# SingleSystem1.net
KiCad netlist of a schematic drawn in EAGLE
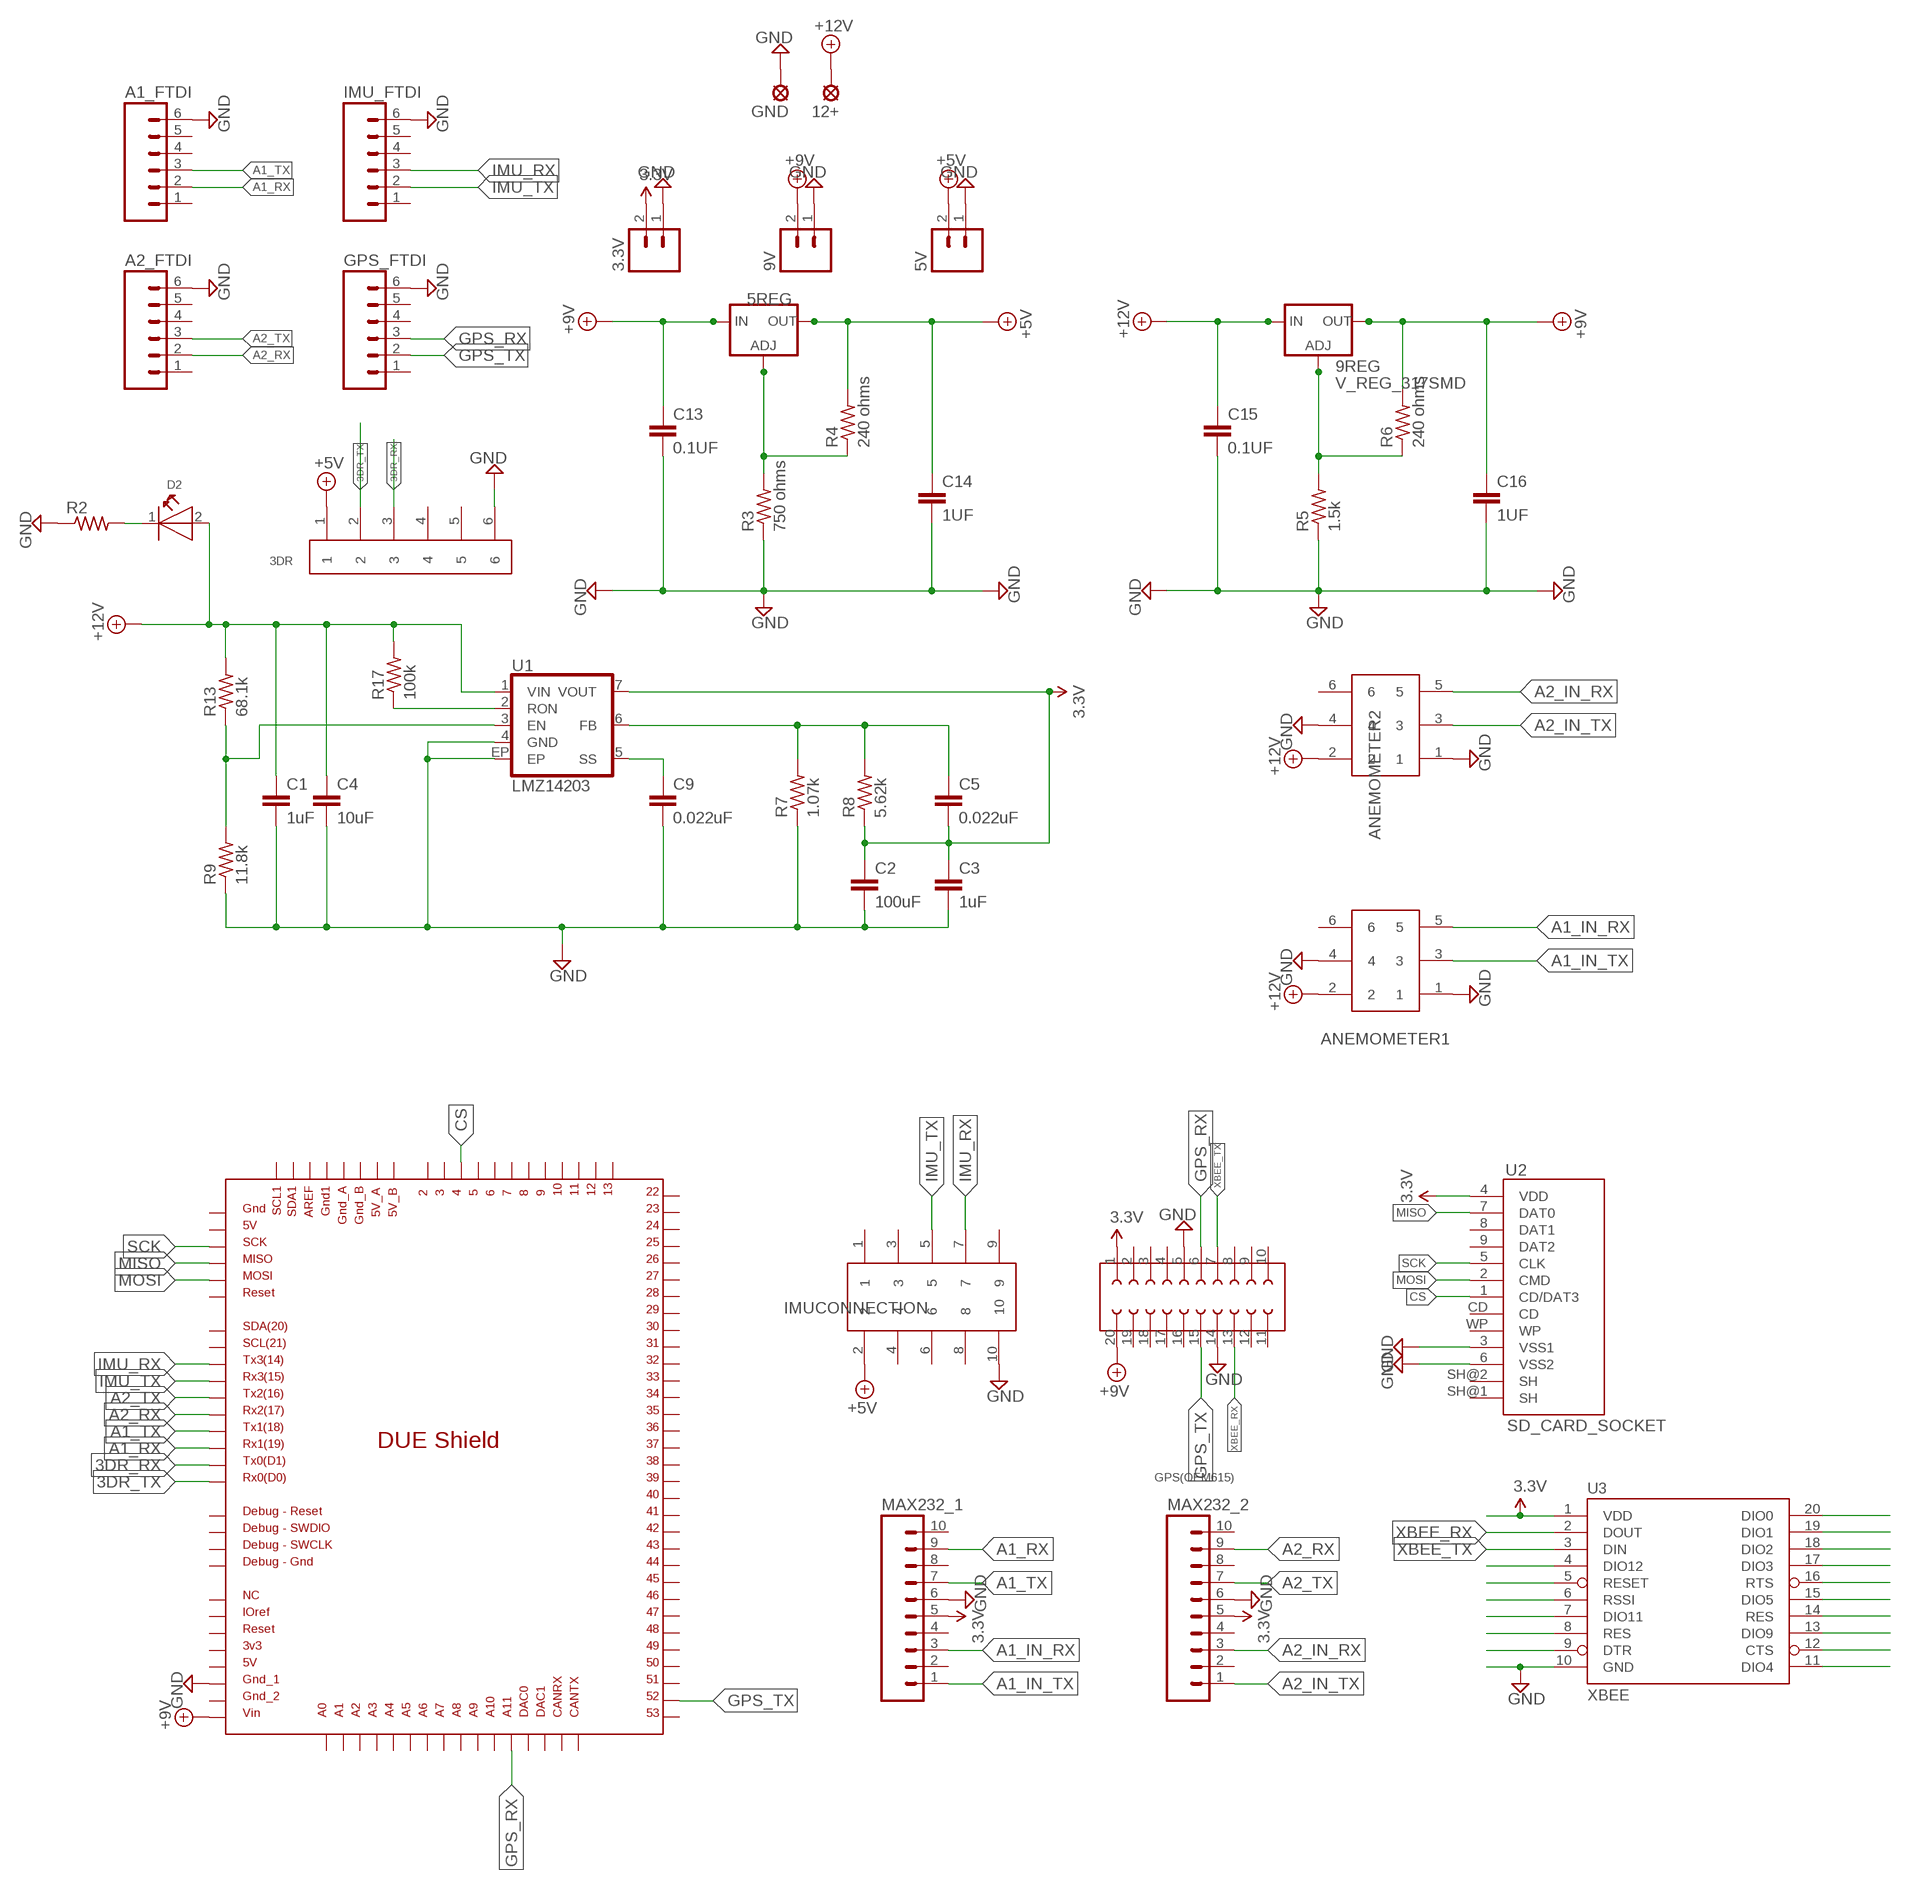
[diagram p0: schematic, sheet 1]

(export (version "E")
  (design (tool "Eeschema 10.0.6"))
  (components
    (comp (ref "3.3V")
      (value "M02")
      (footprint "eagle-import:02P")
      (libsource (lib "eagle-import") (part "M02"))
    )
    (comp (ref "3DR")
      (value "653006114822")
      (footprint "eagle-import:653006114822")
      (libsource (lib "eagle-import") (part "653006114822"))
    )
    (comp (ref "5REG")
      (value "V_REG_317SMD")
      (footprint "eagle-import:SOT223")
      (libsource (lib "eagle-import") (part "V_REG_317SMD"))
    )
    (comp (ref "5V")
      (value "M02")
      (footprint "eagle-import:02P")
      (libsource (lib "eagle-import") (part "M02"))
    )
    (comp (ref "9REG")
      (value "V_REG_317SMD")
      (footprint "eagle-import:SOT223")
      (libsource (lib "eagle-import") (part "V_REG_317SMD"))
    )
    (comp (ref "9V")
      (value "M02")
      (footprint "eagle-import:02P")
      (libsource (lib "eagle-import") (part "M02"))
    )
    (comp (ref "12+")
      (value "SE14")
      (footprint "eagle-import:SE14")
      (libsource (lib "eagle-import") (part "SE14"))
    )
    (comp (ref "A1_FTDI")
      (value "M06")
      (footprint "eagle-import:06P")
      (libsource (lib "eagle-import") (part "M06"))
    )
    (comp (ref "A2_FTDI")
      (value "M06")
      (footprint "eagle-import:06P")
      (libsource (lib "eagle-import") (part "M06"))
    )
    (comp (ref "ANEMOMETER1")
      (value "61200622323")
      (footprint "eagle-import:61200622323")
      (libsource (lib "eagle-import") (part "61200622323"))
    )
    (comp (ref "ANEMOMETER2")
      (value "61200622323")
      (footprint "eagle-import:61200622323")
      (libsource (lib "eagle-import") (part "61200622323"))
    )
    (comp (ref "C1")
      (value "1uF")
      (footprint "eagle-import:0805")
      (fields (field (name "MF") "VISHAY/SPRAGUE") (field (name "MPN") "1C10Z5U104M050R"))
      (libsource (lib "eagle-import") (part "1UF-25V-10%(0805)"))
    )
    (comp (ref "C2")
      (value "100uF")
      (footprint "eagle-import:1206")
      (libsource (lib "eagle-import") (part "CAP1206"))
    )
    (comp (ref "C3")
      (value "1uF")
      (footprint "eagle-import:0805")
      (fields (field (name "MF") "VISHAY/SPRAGUE") (field (name "MPN") "1C10Z5U104M050R"))
      (libsource (lib "eagle-import") (part "1UF-25V-10%(0805)"))
    )
    (comp (ref "C4")
      (value "10uF")
      (footprint "eagle-import:0805")
      (libsource (lib "eagle-import") (part "CAP0805"))
    )
    (comp (ref "C5")
      (value "0.022uF")
      (footprint "eagle-import:0603-CAP")
      (libsource (lib "eagle-import") (part "CAP0603-CAP"))
    )
    (comp (ref "C9")
      (value "0.022uF")
      (footprint "eagle-import:0603-CAP")
      (libsource (lib "eagle-import") (part "CAP0603-CAP"))
    )
    (comp (ref "C13")
      (value "0.1UF")
      (footprint "eagle-import:0805")
      (libsource (lib "eagle-import") (part "1UF-25V-10%(0805)"))
    )
    (comp (ref "C14")
      (value "1UF")
      (footprint "eagle-import:0805")
      (libsource (lib "eagle-import") (part "1UF-25V-10%(0805)"))
    )
    (comp (ref "C15")
      (value "0.1UF")
      (footprint "eagle-import:0805")
      (libsource (lib "eagle-import") (part "1UF-25V-10%(0805)"))
    )
    (comp (ref "C16")
      (value "1UF")
      (footprint "eagle-import:0805")
      (libsource (lib "eagle-import") (part "1UF-25V-10%(0805)"))
    )
    (comp (ref "D2")
      (value "WL-SMCW-150120BS75000-B")
      (footprint "eagle-import:1206")
      (fields
        (field (name "MANUFACTURER") "Würth Elektronik eiSos GmbH")
        (field (name "CREATED-BY") "Christin Otto")
      )
      (libsource (lib "eagle-import") (part "WL-SMCW-150120BS75000-B"))
    )
    (comp (ref "GND")
      (value "SE14")
      (footprint "eagle-import:SE14")
      (libsource (lib "eagle-import") (part "SE14"))
    )
    (comp (ref "GPS(OEM615)")
      (value "62002021821")
      (footprint "eagle-import:62002021821")
      (libsource (lib "eagle-import") (part "62002021821"))
    )
    (comp (ref "GPS_FTDI")
      (value "M06")
      (footprint "eagle-import:06P")
      (libsource (lib "eagle-import") (part "M06"))
    )
    (comp (ref "IMUCONNECTION")
      (value "62501021621")
      (footprint "eagle-import:62501021621")
      (libsource (lib "eagle-import") (part "62501021621"))
    )
    (comp (ref "IMU_FTDI")
      (value "M06")
      (footprint "eagle-import:06P")
      (libsource (lib "eagle-import") (part "M06"))
    )
    (comp (ref "MAX232_1")
      (value "M10")
      (footprint "eagle-import:10P")
      (libsource (lib "eagle-import") (part "M10"))
    )
    (comp (ref "MAX232_2")
      (value "M10")
      (footprint "eagle-import:10P")
      (libsource (lib "eagle-import") (part "M10"))
    )
    (comp (ref "R2")
      (value "R-US_M2012")
      (footprint "eagle-import:M2012")
      (libsource (lib "eagle-import") (part "resistor_R-US_M2012"))
    )
    (comp (ref "R3")
      (value "750 ohms")
      (footprint "eagle-import:M2012")
      (libsource (lib "eagle-import") (part "R-US_M2012"))
    )
    (comp (ref "R4")
      (value "240 ohms")
      (footprint "eagle-import:M2012")
      (libsource (lib "eagle-import") (part "R-US_M2012"))
    )
    (comp (ref "R5")
      (value "1.5k")
      (footprint "eagle-import:M2012")
      (libsource (lib "eagle-import") (part "R-US_M2012"))
    )
    (comp (ref "R6")
      (value "240 ohms")
      (footprint "eagle-import:M2012")
      (libsource (lib "eagle-import") (part "R-US_M2012"))
    )
    (comp (ref "R7")
      (value "1.07k")
      (footprint "eagle-import:M2012")
      (libsource (lib "eagle-import") (part "resistor_R-US_M2012"))
    )
    (comp (ref "R8")
      (value "5.62k")
      (footprint "eagle-import:M2012")
      (libsource (lib "eagle-import") (part "resistor_R-US_M2012"))
    )
    (comp (ref "R9")
      (value "11.8k")
      (footprint "eagle-import:M2012")
      (libsource (lib "eagle-import") (part "resistor_R-US_M2012"))
    )
    (comp (ref "R13")
      (value "68.1k")
      (footprint "eagle-import:M2012")
      (libsource (lib "eagle-import") (part "resistor_R-US_M2012"))
    )
    (comp (ref "R17")
      (value "100k")
      (footprint "eagle-import:M2012")
      (libsource (lib "eagle-import") (part "resistor_R-US_M2012"))
    )
    (comp (ref "U$1")
      (value "DUE(NORMAL)")
      (footprint "eagle-import:DUE(NORMAL)")
      (libsource (lib "eagle-import") (part "DUE(NORMAL)"))
    )
    (comp (ref "U1")
      (value "LMZ14203")
      (footprint "eagle-import:TO-PMOD-7")
      (libsource (lib "eagle-import") (part "LMZ14203"))
    )
    (comp (ref "U2")
      (value "SD_CARD_SOCKET")
      (footprint "eagle-import:SD_1_1")
      (libsource (lib "eagle-import") (part "SD_CARD_SOCKET"))
    )
    (comp (ref "U3")
      (value "XBEE")
      (footprint "eagle-import:XBEE-1")
      (libsource (lib "eagle-import") (part "XBEE-1B1"))
    )
  )
  (nets
    (net (code "1") (name "+5V") (class "Default")
      (node (ref "3DR") (pin "1") (pinfunction "1_1") (pintype "passive"))
      (node (ref "5REG") (pin "2") (pinfunction "OUT_2") (pintype "output"))
      (node (ref "5V") (pin "2") (pinfunction "2_2") (pintype "passive"))
      (node (ref "C14") (pin "1") (pinfunction "1_1") (pintype "passive"))
      (node (ref "IMUCONNECTION") (pin "2") (pinfunction "2_2") (pintype "passive"))
      (node (ref "R4") (pin "2") (pinfunction "2_2") (pintype "passive"))
    )
    (net (code "2") (name "+9V") (class "Default")
      (node (ref "5REG") (pin "3") (pinfunction "IN_3") (pintype "input"))
      (node (ref "9REG") (pin "2") (pinfunction "OUT_2") (pintype "output"))
      (node (ref "9V") (pin "2") (pinfunction "2_2") (pintype "passive"))
      (node (ref "C13") (pin "1") (pinfunction "1_1") (pintype "passive"))
      (node (ref "C16") (pin "1") (pinfunction "1_1") (pintype "passive"))
      (node (ref "GPS(OEM615)") (pin "20") (pinfunction "20_20") (pintype "passive"))
      (node (ref "R6") (pin "2") (pinfunction "2_2") (pintype "passive"))
      (node (ref "U$1") (pin "VIN") (pinfunction "VIN_VIN") (pintype "bidirectional"))
    )
    (net (code "3") (name "+12V") (class "Default")
      (node (ref "12+") (pin "MP") (pinfunction "MP_MP") (pintype "passive"))
      (node (ref "9REG") (pin "3") (pinfunction "IN_3") (pintype "input"))
      (node (ref "ANEMOMETER1") (pin "2") (pinfunction "2_2") (pintype "passive"))
      (node (ref "ANEMOMETER2") (pin "2") (pinfunction "2_2") (pintype "passive"))
      (node (ref "C1") (pin "1") (pinfunction "1_1") (pintype "passive"))
      (node (ref "C15") (pin "1") (pinfunction "1_1") (pintype "passive"))
      (node (ref "C4") (pin "1") (pinfunction "1_1") (pintype "passive"))
      (node (ref "D2") (pin "2") (pinfunction "A_2") (pintype "bidirectional"))
      (node (ref "R13") (pin "2") (pinfunction "2_2") (pintype "passive"))
      (node (ref "R17") (pin "2") (pinfunction "2_2") (pintype "passive"))
      (node (ref "U1") (pin "1") (pinfunction "VIN_1") (pintype "bidirectional"))
    )
    (net (code "4") (name "3.3V") (class "Default")
      (node (ref "3.3V") (pin "2") (pinfunction "2_2") (pintype "passive"))
      (node (ref "C2") (pin "1") (pinfunction "1_1") (pintype "passive"))
      (node (ref "C3") (pin "1") (pinfunction "1_1") (pintype "passive"))
      (node (ref "C5") (pin "2") (pinfunction "2_2") (pintype "passive"))
      (node (ref "GPS(OEM615)") (pin "1") (pinfunction "1_1") (pintype "passive"))
      (node (ref "MAX232_1") (pin "5") (pinfunction "5_5") (pintype "passive"))
      (node (ref "MAX232_2") (pin "5") (pinfunction "5_5") (pintype "passive"))
      (node (ref "R8") (pin "1") (pinfunction "1_1") (pintype "passive"))
      (node (ref "U1") (pin "7") (pinfunction "VOUT_7") (pintype "bidirectional"))
      (node (ref "U2") (pin "4") (pinfunction "VDD_4") (pintype "power_in"))
      (node (ref "U3") (pin "1") (pinfunction "VDD_1") (pintype "power_in"))
    )
    (net (code "5") (name "3DR_RX") (class "Default")
      (node (ref "3DR") (pin "3") (pinfunction "3_3") (pintype "passive"))
      (node (ref "U$1") (pin "TX0") (pinfunction "TX0_TX0") (pintype "bidirectional"))
    )
    (net (code "6") (name "3DR_TX") (class "Default")
      (node (ref "3DR") (pin "2") (pinfunction "2_2") (pintype "passive"))
      (node (ref "U$1") (pin "RX0") (pinfunction "RX0_RX0") (pintype "bidirectional"))
    )
    (net (code "7") (name "A1_IN_RX") (class "Default")
      (node (ref "ANEMOMETER1") (pin "5") (pinfunction "5_5") (pintype "passive"))
      (node (ref "MAX232_1") (pin "3") (pinfunction "3_3") (pintype "passive"))
    )
    (net (code "8") (name "A1_IN_TX") (class "Default")
      (node (ref "ANEMOMETER1") (pin "3") (pinfunction "3_3") (pintype "passive"))
      (node (ref "MAX232_1") (pin "1") (pinfunction "1_1") (pintype "passive"))
    )
    (net (code "9") (name "A1_RX") (class "Default")
      (node (ref "A1_FTDI") (pin "2") (pinfunction "2_2") (pintype "passive"))
      (node (ref "MAX232_1") (pin "9") (pinfunction "9_9") (pintype "passive"))
      (node (ref "U$1") (pin "RX1") (pinfunction "RX1_RX1") (pintype "bidirectional"))
    )
    (net (code "10") (name "A1_TX") (class "Default")
      (node (ref "A1_FTDI") (pin "3") (pinfunction "3_3") (pintype "passive"))
      (node (ref "MAX232_1") (pin "7") (pinfunction "7_7") (pintype "passive"))
      (node (ref "U$1") (pin "TX1") (pinfunction "TX1_TX1") (pintype "bidirectional"))
    )
    (net (code "11") (name "A2_IN_RX") (class "Default")
      (node (ref "ANEMOMETER2") (pin "5") (pinfunction "5_5") (pintype "passive"))
      (node (ref "MAX232_2") (pin "3") (pinfunction "3_3") (pintype "passive"))
    )
    (net (code "12") (name "A2_IN_TX") (class "Default")
      (node (ref "ANEMOMETER2") (pin "3") (pinfunction "3_3") (pintype "passive"))
      (node (ref "MAX232_2") (pin "1") (pinfunction "1_1") (pintype "passive"))
    )
    (net (code "13") (name "A2_RX") (class "Default")
      (node (ref "A2_FTDI") (pin "2") (pinfunction "2_2") (pintype "passive"))
      (node (ref "MAX232_2") (pin "9") (pinfunction "9_9") (pintype "passive"))
      (node (ref "U$1") (pin "RX2") (pinfunction "RX2_RX2") (pintype "bidirectional"))
    )
    (net (code "14") (name "A2_TX") (class "Default")
      (node (ref "A2_FTDI") (pin "3") (pinfunction "3_3") (pintype "passive"))
      (node (ref "MAX232_2") (pin "7") (pinfunction "7_7") (pintype "passive"))
      (node (ref "U$1") (pin "TX2") (pinfunction "TX2_TX2") (pintype "bidirectional"))
    )
    (net (code "15") (name "CS") (class "Default")
      (node (ref "U$1") (pin "4") (pinfunction "4_4") (pintype "bidirectional"))
      (node (ref "U2") (pin "1") (pinfunction "CD/DAT3_1") (pintype "bidirectional"))
    )
    (net (code "16") (name "GND") (class "Default")
      (node (ref "3.3V") (pin "1") (pinfunction "1_1") (pintype "passive"))
      (node (ref "3DR") (pin "6") (pinfunction "6_6") (pintype "passive"))
      (node (ref "5V") (pin "1") (pinfunction "1_1") (pintype "passive"))
      (node (ref "9V") (pin "1") (pinfunction "1_1") (pintype "passive"))
      (node (ref "A1_FTDI") (pin "6") (pinfunction "6_6") (pintype "passive"))
      (node (ref "A2_FTDI") (pin "6") (pinfunction "6_6") (pintype "passive"))
      (node (ref "ANEMOMETER1") (pin "1") (pinfunction "1_1") (pintype "passive"))
      (node (ref "ANEMOMETER1") (pin "4") (pinfunction "4_4") (pintype "passive"))
      (node (ref "ANEMOMETER2") (pin "1") (pinfunction "1_1") (pintype "passive"))
      (node (ref "ANEMOMETER2") (pin "4") (pinfunction "4_4") (pintype "passive"))
      (node (ref "C1") (pin "2") (pinfunction "2_2") (pintype "passive"))
      (node (ref "C13") (pin "2") (pinfunction "2_2") (pintype "passive"))
      (node (ref "C14") (pin "2") (pinfunction "2_2") (pintype "passive"))
      (node (ref "C15") (pin "2") (pinfunction "2_2") (pintype "passive"))
      (node (ref "C16") (pin "2") (pinfunction "2_2") (pintype "passive"))
      (node (ref "C2") (pin "2") (pinfunction "2_2") (pintype "passive"))
      (node (ref "C3") (pin "2") (pinfunction "2_2") (pintype "passive"))
      (node (ref "C4") (pin "2") (pinfunction "2_2") (pintype "passive"))
      (node (ref "C9") (pin "2") (pinfunction "2_2") (pintype "passive"))
      (node (ref "GND") (pin "MP") (pinfunction "MP_MP") (pintype "passive"))
      (node (ref "GPS(OEM615)") (pin "14") (pinfunction "14_14") (pintype "passive"))
      (node (ref "GPS(OEM615)") (pin "5") (pinfunction "5_5") (pintype "passive"))
      (node (ref "GPS_FTDI") (pin "6") (pinfunction "6_6") (pintype "passive"))
      (node (ref "IMUCONNECTION") (pin "10") (pinfunction "10_10") (pintype "passive"))
      (node (ref "IMU_FTDI") (pin "6") (pinfunction "6_6") (pintype "passive"))
      (node (ref "MAX232_1") (pin "6") (pinfunction "6_6") (pintype "passive"))
      (node (ref "MAX232_2") (pin "6") (pinfunction "6_6") (pintype "passive"))
      (node (ref "R2") (pin "1") (pinfunction "1_1") (pintype "passive"))
      (node (ref "R3") (pin "1") (pinfunction "1_1") (pintype "passive"))
      (node (ref "R5") (pin "1") (pinfunction "1_1") (pintype "passive"))
      (node (ref "R7") (pin "1") (pinfunction "1_1") (pintype "passive"))
      (node (ref "R9") (pin "1") (pinfunction "1_1") (pintype "passive"))
      (node (ref "U$1") (pin "GND_1") (pinfunction "GND_1_GND_1") (pintype "bidirectional"))
      (node (ref "U1") (pin "4") (pinfunction "GND_4") (pintype "bidirectional"))
      (node (ref "U1") (pin "EP") (pinfunction "EP_EP") (pintype "bidirectional"))
      (node (ref "U2") (pin "3") (pinfunction "VSS1_3") (pintype "power_in"))
      (node (ref "U2") (pin "6") (pinfunction "VSS2_6") (pintype "power_in"))
      (node (ref "U3") (pin "10") (pinfunction "GND_10") (pintype "power_in"))
    )
    (net (code "17") (name "GPS_RX") (class "Default")
      (node (ref "GPS(OEM615)") (pin "6") (pinfunction "6_6") (pintype "passive"))
      (node (ref "GPS_FTDI") (pin "3") (pinfunction "3_3") (pintype "passive"))
      (node (ref "U$1") (pin "A11") (pinfunction "A11_A11") (pintype "bidirectional"))
    )
    (net (code "18") (name "GPS_TX") (class "Default")
      (node (ref "GPS(OEM615)") (pin "15") (pinfunction "15_15") (pintype "passive"))
      (node (ref "GPS_FTDI") (pin "2") (pinfunction "2_2") (pintype "passive"))
      (node (ref "U$1") (pin "52") (pinfunction "52_52") (pintype "bidirectional"))
    )
    (net (code "19") (name "IMU_RX") (class "Default")
      (node (ref "IMUCONNECTION") (pin "7") (pinfunction "7_7") (pintype "passive"))
      (node (ref "IMU_FTDI") (pin "3") (pinfunction "3_3") (pintype "passive"))
      (node (ref "U$1") (pin "TX3") (pinfunction "TX3_TX3") (pintype "bidirectional"))
    )
    (net (code "20") (name "IMU_TX") (class "Default")
      (node (ref "IMUCONNECTION") (pin "5") (pinfunction "5_5") (pintype "passive"))
      (node (ref "IMU_FTDI") (pin "2") (pinfunction "2_2") (pintype "passive"))
      (node (ref "U$1") (pin "RX3") (pinfunction "RX3_RX3") (pintype "bidirectional"))
    )
    (net (code "21") (name "MISO") (class "Default")
      (node (ref "U$1") (pin "MISO_ICSP") (pinfunction "MISO_ICSP_MISO_ICSP") (pintype "bidirectional"))
      (node (ref "U2") (pin "7") (pinfunction "DAT0_7") (pintype "bidirectional"))
    )
    (net (code "22") (name "MOSI") (class "Default")
      (node (ref "U$1") (pin "MOSI_ICSP") (pinfunction "MOSI_ICSP_MOSI_ICSP") (pintype "bidirectional"))
      (node (ref "U2") (pin "2") (pinfunction "CMD_2") (pintype "bidirectional"))
    )
    (net (code "23") (name "Net-(5REG-ADJ)") (class "Default")
      (node (ref "5REG") (pin "1") (pinfunction "ADJ_1") (pintype "input"))
      (node (ref "R3") (pin "2") (pinfunction "2_2") (pintype "passive"))
      (node (ref "R4") (pin "1") (pinfunction "1_1") (pintype "passive"))
    )
    (net (code "24") (name "Net-(9REG-ADJ)") (class "Default")
      (node (ref "9REG") (pin "1") (pinfunction "ADJ_1") (pintype "input"))
      (node (ref "R5") (pin "2") (pinfunction "2_2") (pintype "passive"))
      (node (ref "R6") (pin "1") (pinfunction "1_1") (pintype "passive"))
    )
    (net (code "25") (name "Net-(D2-K)") (class "Default")
      (node (ref "D2") (pin "1") (pinfunction "K_1") (pintype "bidirectional"))
      (node (ref "R2") (pin "2") (pinfunction "2_2") (pintype "passive"))
    )
    (net (code "26") (name "Net-(U1-EN)") (class "Default")
      (node (ref "R13") (pin "1") (pinfunction "1_1") (pintype "passive"))
      (node (ref "R9") (pin "2") (pinfunction "2_2") (pintype "passive"))
      (node (ref "U1") (pin "3") (pinfunction "EN_3") (pintype "bidirectional"))
    )
    (net (code "27") (name "Net-(U1-FB)") (class "Default")
      (node (ref "C5") (pin "1") (pinfunction "1_1") (pintype "passive"))
      (node (ref "R7") (pin "2") (pinfunction "2_2") (pintype "passive"))
      (node (ref "R8") (pin "2") (pinfunction "2_2") (pintype "passive"))
      (node (ref "U1") (pin "6") (pinfunction "FB_6") (pintype "bidirectional"))
    )
    (net (code "28") (name "Net-(U1-RON)") (class "Default")
      (node (ref "R17") (pin "1") (pinfunction "1_1") (pintype "passive"))
      (node (ref "U1") (pin "2") (pinfunction "RON_2") (pintype "bidirectional"))
    )
    (net (code "29") (name "Net-(U1-SS)") (class "Default")
      (node (ref "C9") (pin "1") (pinfunction "1_1") (pintype "passive"))
      (node (ref "U1") (pin "5") (pinfunction "SS_5") (pintype "bidirectional"))
    )
    (net (code "30") (name "SCK") (class "Default")
      (node (ref "U$1") (pin "SCK_ICSP") (pinfunction "SCK_ICSP_SCK_ICSP") (pintype "bidirectional"))
      (node (ref "U2") (pin "5") (pinfunction "CLK_5") (pintype "bidirectional"))
    )
    (net (code "31") (name "XBEE_RX") (class "Default")
      (node (ref "GPS(OEM615)") (pin "13") (pinfunction "13_13") (pintype "passive"))
      (node (ref "U3") (pin "2") (pinfunction "DOUT_2") (pintype "output"))
    )
    (net (code "32") (name "XBEE_TX") (class "Default")
      (node (ref "GPS(OEM615)") (pin "7") (pinfunction "7_7") (pintype "passive"))
      (node (ref "U3") (pin "3") (pinfunction "DIN_3") (pintype "input"))
    )
    (net (code "33") (name "unconnected-(3DR-Pad4)") (class "Default")
      (node (ref "3DR") (pin "4") (pinfunction "4_4") (pintype "passive"))
    )
    (net (code "34") (name "unconnected-(3DR-Pad5)") (class "Default")
      (node (ref "3DR") (pin "5") (pinfunction "5_5") (pintype "passive"))
    )
    (net (code "35") (name "unconnected-(A1_FTDI-Pad1)") (class "Default")
      (node (ref "A1_FTDI") (pin "1") (pinfunction "1_1") (pintype "passive"))
    )
    (net (code "36") (name "unconnected-(A1_FTDI-Pad4)") (class "Default")
      (node (ref "A1_FTDI") (pin "4") (pinfunction "4_4") (pintype "passive"))
    )
    (net (code "37") (name "unconnected-(A1_FTDI-Pad5)") (class "Default")
      (node (ref "A1_FTDI") (pin "5") (pinfunction "5_5") (pintype "passive"))
    )
    (net (code "38") (name "unconnected-(A2_FTDI-Pad1)") (class "Default")
      (node (ref "A2_FTDI") (pin "1") (pinfunction "1_1") (pintype "passive"))
    )
    (net (code "39") (name "unconnected-(A2_FTDI-Pad4)") (class "Default")
      (node (ref "A2_FTDI") (pin "4") (pinfunction "4_4") (pintype "passive"))
    )
    (net (code "40") (name "unconnected-(A2_FTDI-Pad5)") (class "Default")
      (node (ref "A2_FTDI") (pin "5") (pinfunction "5_5") (pintype "passive"))
    )
    (net (code "41") (name "unconnected-(ANEMOMETER1-Pad6)") (class "Default")
      (node (ref "ANEMOMETER1") (pin "6") (pinfunction "6_6") (pintype "passive"))
    )
    (net (code "42") (name "unconnected-(ANEMOMETER2-Pad6)") (class "Default")
      (node (ref "ANEMOMETER2") (pin "6") (pinfunction "6_6") (pintype "passive"))
    )
    (net (code "43") (name "unconnected-(GPS(OEM615)-Pad2)") (class "Default")
      (node (ref "GPS(OEM615)") (pin "2") (pinfunction "2_2") (pintype "passive"))
    )
    (net (code "44") (name "unconnected-(GPS(OEM615)-Pad3)") (class "Default")
      (node (ref "GPS(OEM615)") (pin "3") (pinfunction "3_3") (pintype "passive"))
    )
    (net (code "45") (name "unconnected-(GPS(OEM615)-Pad4)") (class "Default")
      (node (ref "GPS(OEM615)") (pin "4") (pinfunction "4_4") (pintype "passive"))
    )
    (net (code "46") (name "unconnected-(GPS(OEM615)-Pad8)") (class "Default")
      (node (ref "GPS(OEM615)") (pin "8") (pinfunction "8_8") (pintype "passive"))
    )
    (net (code "47") (name "unconnected-(GPS(OEM615)-Pad9)") (class "Default")
      (node (ref "GPS(OEM615)") (pin "9") (pinfunction "9_9") (pintype "passive"))
    )
    (net (code "48") (name "unconnected-(GPS(OEM615)-Pad10)") (class "Default")
      (node (ref "GPS(OEM615)") (pin "10") (pinfunction "10_10") (pintype "passive"))
    )
    (net (code "49") (name "unconnected-(GPS(OEM615)-Pad11)") (class "Default")
      (node (ref "GPS(OEM615)") (pin "11") (pinfunction "11_11") (pintype "passive"))
    )
    (net (code "50") (name "unconnected-(GPS(OEM615)-Pad12)") (class "Default")
      (node (ref "GPS(OEM615)") (pin "12") (pinfunction "12_12") (pintype "passive"))
    )
    (net (code "51") (name "unconnected-(GPS(OEM615)-Pad16)") (class "Default")
      (node (ref "GPS(OEM615)") (pin "16") (pinfunction "16_16") (pintype "passive"))
    )
    (net (code "52") (name "unconnected-(GPS(OEM615)-Pad17)") (class "Default")
      (node (ref "GPS(OEM615)") (pin "17") (pinfunction "17_17") (pintype "passive"))
    )
    (net (code "53") (name "unconnected-(GPS(OEM615)-Pad18)") (class "Default")
      (node (ref "GPS(OEM615)") (pin "18") (pinfunction "18_18") (pintype "passive"))
    )
    (net (code "54") (name "unconnected-(GPS(OEM615)-Pad19)") (class "Default")
      (node (ref "GPS(OEM615)") (pin "19") (pinfunction "19_19") (pintype "passive"))
    )
    (net (code "55") (name "unconnected-(GPS_FTDI-Pad1)") (class "Default")
      (node (ref "GPS_FTDI") (pin "1") (pinfunction "1_1") (pintype "passive"))
    )
    (net (code "56") (name "unconnected-(GPS_FTDI-Pad4)") (class "Default")
      (node (ref "GPS_FTDI") (pin "4") (pinfunction "4_4") (pintype "passive"))
    )
    (net (code "57") (name "unconnected-(GPS_FTDI-Pad5)") (class "Default")
      (node (ref "GPS_FTDI") (pin "5") (pinfunction "5_5") (pintype "passive"))
    )
    (net (code "58") (name "unconnected-(IMUCONNECTION-Pad1)") (class "Default")
      (node (ref "IMUCONNECTION") (pin "1") (pinfunction "1_1") (pintype "passive"))
    )
    (net (code "59") (name "unconnected-(IMUCONNECTION-Pad3)") (class "Default")
      (node (ref "IMUCONNECTION") (pin "3") (pinfunction "3_3") (pintype "passive"))
    )
    (net (code "60") (name "unconnected-(IMUCONNECTION-Pad4)") (class "Default")
      (node (ref "IMUCONNECTION") (pin "4") (pinfunction "4_4") (pintype "passive"))
    )
    (net (code "61") (name "unconnected-(IMUCONNECTION-Pad6)") (class "Default")
      (node (ref "IMUCONNECTION") (pin "6") (pinfunction "6_6") (pintype "passive"))
    )
    (net (code "62") (name "unconnected-(IMUCONNECTION-Pad8)") (class "Default")
      (node (ref "IMUCONNECTION") (pin "8") (pinfunction "8_8") (pintype "passive"))
    )
    (net (code "63") (name "unconnected-(IMUCONNECTION-Pad9)") (class "Default")
      (node (ref "IMUCONNECTION") (pin "9") (pinfunction "9_9") (pintype "passive"))
    )
    (net (code "64") (name "unconnected-(IMU_FTDI-Pad1)") (class "Default")
      (node (ref "IMU_FTDI") (pin "1") (pinfunction "1_1") (pintype "passive"))
    )
    (net (code "65") (name "unconnected-(IMU_FTDI-Pad4)") (class "Default")
      (node (ref "IMU_FTDI") (pin "4") (pinfunction "4_4") (pintype "passive"))
    )
    (net (code "66") (name "unconnected-(IMU_FTDI-Pad5)") (class "Default")
      (node (ref "IMU_FTDI") (pin "5") (pinfunction "5_5") (pintype "passive"))
    )
    (net (code "67") (name "unconnected-(MAX232_1-Pad2)") (class "Default")
      (node (ref "MAX232_1") (pin "2") (pinfunction "2_2") (pintype "passive"))
    )
    (net (code "68") (name "unconnected-(MAX232_1-Pad4)") (class "Default")
      (node (ref "MAX232_1") (pin "4") (pinfunction "4_4") (pintype "passive"))
    )
    (net (code "69") (name "unconnected-(MAX232_1-Pad8)") (class "Default")
      (node (ref "MAX232_1") (pin "8") (pinfunction "8_8") (pintype "passive"))
    )
    (net (code "70") (name "unconnected-(MAX232_1-Pad10)") (class "Default")
      (node (ref "MAX232_1") (pin "10") (pinfunction "10_10") (pintype "passive"))
    )
    (net (code "71") (name "unconnected-(MAX232_2-Pad2)") (class "Default")
      (node (ref "MAX232_2") (pin "2") (pinfunction "2_2") (pintype "passive"))
    )
    (net (code "72") (name "unconnected-(MAX232_2-Pad4)") (class "Default")
      (node (ref "MAX232_2") (pin "4") (pinfunction "4_4") (pintype "passive"))
    )
    (net (code "73") (name "unconnected-(MAX232_2-Pad8)") (class "Default")
      (node (ref "MAX232_2") (pin "8") (pinfunction "8_8") (pintype "passive"))
    )
    (net (code "74") (name "unconnected-(MAX232_2-Pad10)") (class "Default")
      (node (ref "MAX232_2") (pin "10") (pinfunction "10_10") (pintype "passive"))
    )
    (net (code "75") (name "unconnected-(U$1-Pad2)") (class "Default")
      (node (ref "U$1") (pin "2") (pinfunction "2_2") (pintype "bidirectional"))
    )
    (net (code "76") (name "unconnected-(U$1-Pad3)") (class "Default")
      (node (ref "U$1") (pin "3") (pinfunction "3_3") (pintype "bidirectional"))
    )
    (net (code "77") (name "unconnected-(U$1-Pad3V3)") (class "Default")
      (node (ref "U$1") (pin "3V3") (pinfunction "3V3_3V3") (pintype "bidirectional"))
    )
    (net (code "78") (name "unconnected-(U$1-Pad5)") (class "Default")
      (node (ref "U$1") (pin "5") (pinfunction "5_5") (pintype "bidirectional"))
    )
    (net (code "79") (name "unconnected-(U$1-Pad5V)") (class "Default")
      (node (ref "U$1") (pin "5V") (pinfunction "5V_5V") (pintype "bidirectional"))
    )
    (net (code "80") (name "unconnected-(U$1-Pad5V_A)") (class "Default")
      (node (ref "U$1") (pin "5V_A") (pinfunction "5V_A_5V_A") (pintype "bidirectional"))
    )
    (net (code "81") (name "unconnected-(U$1-Pad5V_B)") (class "Default")
      (node (ref "U$1") (pin "5V_B") (pinfunction "5V_B_5V_B") (pintype "bidirectional"))
    )
    (net (code "82") (name "unconnected-(U$1-Pad5V_ICSP)") (class "Default")
      (node (ref "U$1") (pin "5V_ICSP") (pinfunction "5V_ICSP_5V_ICSP") (pintype "bidirectional"))
    )
    (net (code "83") (name "unconnected-(U$1-Pad6)") (class "Default")
      (node (ref "U$1") (pin "6") (pinfunction "6_6") (pintype "bidirectional"))
    )
    (net (code "84") (name "unconnected-(U$1-Pad7)") (class "Default")
      (node (ref "U$1") (pin "7") (pinfunction "7_7") (pintype "bidirectional"))
    )
    (net (code "85") (name "unconnected-(U$1-Pad8)") (class "Default")
      (node (ref "U$1") (pin "8") (pinfunction "8_8") (pintype "bidirectional"))
    )
    (net (code "86") (name "unconnected-(U$1-Pad9)") (class "Default")
      (node (ref "U$1") (pin "9") (pinfunction "9_9") (pintype "bidirectional"))
    )
    (net (code "87") (name "unconnected-(U$1-Pad10)") (class "Default")
      (node (ref "U$1") (pin "10") (pinfunction "10_10") (pintype "bidirectional"))
    )
    (net (code "88") (name "unconnected-(U$1-Pad11)") (class "Default")
      (node (ref "U$1") (pin "11") (pinfunction "11_11") (pintype "bidirectional"))
    )
    (net (code "89") (name "unconnected-(U$1-Pad12)") (class "Default")
      (node (ref "U$1") (pin "12") (pinfunction "12_12") (pintype "bidirectional"))
    )
    (net (code "90") (name "unconnected-(U$1-Pad13)") (class "Default")
      (node (ref "U$1") (pin "13") (pinfunction "13_13") (pintype "bidirectional"))
    )
    (net (code "91") (name "unconnected-(U$1-Pad22)") (class "Default")
      (node (ref "U$1") (pin "22") (pinfunction "22_22") (pintype "bidirectional"))
    )
    (net (code "92") (name "unconnected-(U$1-Pad23)") (class "Default")
      (node (ref "U$1") (pin "23") (pinfunction "23_23") (pintype "bidirectional"))
    )
    (net (code "93") (name "unconnected-(U$1-Pad24)") (class "Default")
      (node (ref "U$1") (pin "24") (pinfunction "24_24") (pintype "bidirectional"))
    )
    (net (code "94") (name "unconnected-(U$1-Pad25)") (class "Default")
      (node (ref "U$1") (pin "25") (pinfunction "25_25") (pintype "bidirectional"))
    )
    (net (code "95") (name "unconnected-(U$1-Pad26)") (class "Default")
      (node (ref "U$1") (pin "26") (pinfunction "26_26") (pintype "bidirectional"))
    )
    (net (code "96") (name "unconnected-(U$1-Pad27)") (class "Default")
      (node (ref "U$1") (pin "27") (pinfunction "27_27") (pintype "bidirectional"))
    )
    (net (code "97") (name "unconnected-(U$1-Pad28)") (class "Default")
      (node (ref "U$1") (pin "28") (pinfunction "28_28") (pintype "bidirectional"))
    )
    (net (code "98") (name "unconnected-(U$1-Pad29)") (class "Default")
      (node (ref "U$1") (pin "29") (pinfunction "29_29") (pintype "bidirectional"))
    )
    (net (code "99") (name "unconnected-(U$1-Pad30)") (class "Default")
      (node (ref "U$1") (pin "30") (pinfunction "30_30") (pintype "bidirectional"))
    )
    (net (code "100") (name "unconnected-(U$1-Pad31)") (class "Default")
      (node (ref "U$1") (pin "31") (pinfunction "31_31") (pintype "bidirectional"))
    )
    (net (code "101") (name "unconnected-(U$1-Pad32)") (class "Default")
      (node (ref "U$1") (pin "32") (pinfunction "32_32") (pintype "bidirectional"))
    )
    (net (code "102") (name "unconnected-(U$1-Pad33)") (class "Default")
      (node (ref "U$1") (pin "33") (pinfunction "33_33") (pintype "bidirectional"))
    )
    (net (code "103") (name "unconnected-(U$1-Pad34)") (class "Default")
      (node (ref "U$1") (pin "34") (pinfunction "34_34") (pintype "bidirectional"))
    )
    (net (code "104") (name "unconnected-(U$1-Pad35)") (class "Default")
      (node (ref "U$1") (pin "35") (pinfunction "35_35") (pintype "bidirectional"))
    )
    (net (code "105") (name "unconnected-(U$1-Pad36)") (class "Default")
      (node (ref "U$1") (pin "36") (pinfunction "36_36") (pintype "bidirectional"))
    )
    (net (code "106") (name "unconnected-(U$1-Pad37)") (class "Default")
      (node (ref "U$1") (pin "37") (pinfunction "37_37") (pintype "bidirectional"))
    )
    (net (code "107") (name "unconnected-(U$1-Pad38)") (class "Default")
      (node (ref "U$1") (pin "38") (pinfunction "38_38") (pintype "bidirectional"))
    )
    (net (code "108") (name "unconnected-(U$1-Pad39)") (class "Default")
      (node (ref "U$1") (pin "39") (pinfunction "39_39") (pintype "bidirectional"))
    )
    (net (code "109") (name "unconnected-(U$1-Pad40)") (class "Default")
      (node (ref "U$1") (pin "40") (pinfunction "40_40") (pintype "bidirectional"))
    )
    (net (code "110") (name "unconnected-(U$1-Pad41)") (class "Default")
      (node (ref "U$1") (pin "41") (pinfunction "41_41") (pintype "bidirectional"))
    )
    (net (code "111") (name "unconnected-(U$1-Pad42)") (class "Default")
      (node (ref "U$1") (pin "42") (pinfunction "42_42") (pintype "bidirectional"))
    )
    (net (code "112") (name "unconnected-(U$1-Pad43)") (class "Default")
      (node (ref "U$1") (pin "43") (pinfunction "43_43") (pintype "bidirectional"))
    )
    (net (code "113") (name "unconnected-(U$1-Pad44)") (class "Default")
      (node (ref "U$1") (pin "44") (pinfunction "44_44") (pintype "bidirectional"))
    )
    (net (code "114") (name "unconnected-(U$1-Pad45)") (class "Default")
      (node (ref "U$1") (pin "45") (pinfunction "45_45") (pintype "bidirectional"))
    )
    (net (code "115") (name "unconnected-(U$1-Pad46)") (class "Default")
      (node (ref "U$1") (pin "46") (pinfunction "46_46") (pintype "bidirectional"))
    )
    (net (code "116") (name "unconnected-(U$1-Pad47)") (class "Default")
      (node (ref "U$1") (pin "47") (pinfunction "47_47") (pintype "bidirectional"))
    )
    (net (code "117") (name "unconnected-(U$1-Pad48)") (class "Default")
      (node (ref "U$1") (pin "48") (pinfunction "48_48") (pintype "bidirectional"))
    )
    (net (code "118") (name "unconnected-(U$1-Pad49)") (class "Default")
      (node (ref "U$1") (pin "49") (pinfunction "49_49") (pintype "bidirectional"))
    )
    (net (code "119") (name "unconnected-(U$1-Pad50)") (class "Default")
      (node (ref "U$1") (pin "50") (pinfunction "50_50") (pintype "bidirectional"))
    )
    (net (code "120") (name "unconnected-(U$1-Pad51)") (class "Default")
      (node (ref "U$1") (pin "51") (pinfunction "51_51") (pintype "bidirectional"))
    )
    (net (code "121") (name "unconnected-(U$1-Pad53)") (class "Default")
      (node (ref "U$1") (pin "53") (pinfunction "53_53") (pintype "bidirectional"))
    )
    (net (code "122") (name "unconnected-(U$1-PadA0)") (class "Default")
      (node (ref "U$1") (pin "A0") (pinfunction "A0_A0") (pintype "bidirectional"))
    )
    (net (code "123") (name "unconnected-(U$1-PadA1)") (class "Default")
      (node (ref "U$1") (pin "A1") (pinfunction "A1_A1") (pintype "bidirectional"))
    )
    (net (code "124") (name "unconnected-(U$1-PadA2)") (class "Default")
      (node (ref "U$1") (pin "A2") (pinfunction "A2_A2") (pintype "bidirectional"))
    )
    (net (code "125") (name "unconnected-(U$1-PadA3)") (class "Default")
      (node (ref "U$1") (pin "A3") (pinfunction "A3_A3") (pintype "bidirectional"))
    )
    (net (code "126") (name "unconnected-(U$1-PadA4)") (class "Default")
      (node (ref "U$1") (pin "A4") (pinfunction "A4_A4") (pintype "bidirectional"))
    )
    (net (code "127") (name "unconnected-(U$1-PadA5)") (class "Default")
      (node (ref "U$1") (pin "A5") (pinfunction "A5_A5") (pintype "bidirectional"))
    )
    (net (code "128") (name "unconnected-(U$1-PadA6)") (class "Default")
      (node (ref "U$1") (pin "A6") (pinfunction "A6_A6") (pintype "bidirectional"))
    )
    (net (code "129") (name "unconnected-(U$1-PadA7)") (class "Default")
      (node (ref "U$1") (pin "A7") (pinfunction "A7_A7") (pintype "bidirectional"))
    )
    (net (code "130") (name "unconnected-(U$1-PadA8)") (class "Default")
      (node (ref "U$1") (pin "A8") (pinfunction "A8_A8") (pintype "bidirectional"))
    )
    (net (code "131") (name "unconnected-(U$1-PadA9)") (class "Default")
      (node (ref "U$1") (pin "A9") (pinfunction "A9_A9") (pintype "bidirectional"))
    )
    (net (code "132") (name "unconnected-(U$1-PadA10)") (class "Default")
      (node (ref "U$1") (pin "A10") (pinfunction "A10_A10") (pintype "bidirectional"))
    )
    (net (code "133") (name "unconnected-(U$1-PadAREF)") (class "Default")
      (node (ref "U$1") (pin "AREF") (pinfunction "AREF_AREF") (pintype "bidirectional"))
    )
    (net (code "134") (name "unconnected-(U$1-PadCANRX)") (class "Default")
      (node (ref "U$1") (pin "CANRX") (pinfunction "CANRX_CANRX") (pintype "bidirectional"))
    )
    (net (code "135") (name "unconnected-(U$1-PadCANTX)") (class "Default")
      (node (ref "U$1") (pin "CANTX") (pinfunction "CANTX_CANTX") (pintype "bidirectional"))
    )
    (net (code "136") (name "unconnected-(U$1-PadDAC0)") (class "Default")
      (node (ref "U$1") (pin "DAC0") (pinfunction "DAC0_DAC0") (pintype "bidirectional"))
    )
    (net (code "137") (name "unconnected-(U$1-PadDAC1)") (class "Default")
      (node (ref "U$1") (pin "DAC1") (pinfunction "DAC1_DAC1") (pintype "bidirectional"))
    )
    (net (code "138") (name "unconnected-(U$1-PadGND1)") (class "Default")
      (node (ref "U$1") (pin "GND1") (pinfunction "GND1_GND1") (pintype "bidirectional"))
    )
    (net (code "139") (name "unconnected-(U$1-PadGND_2)") (class "Default")
      (node (ref "U$1") (pin "GND_2") (pinfunction "GND_2_GND_2") (pintype "bidirectional"))
    )
    (net (code "140") (name "unconnected-(U$1-PadGND_A)") (class "Default")
      (node (ref "U$1") (pin "GND_A") (pinfunction "GND_A_GND_A") (pintype "bidirectional"))
    )
    (net (code "141") (name "unconnected-(U$1-PadGND_B)") (class "Default")
      (node (ref "U$1") (pin "GND_B") (pinfunction "GND_B_GND_B") (pintype "bidirectional"))
    )
    (net (code "142") (name "unconnected-(U$1-PadGND_DEBUG)") (class "Default")
      (node (ref "U$1") (pin "GND_DEBUG") (pinfunction "GND_DEBUG_GND_DEBUG") (pintype "bidirectional"))
    )
    (net (code "143") (name "unconnected-(U$1-PadGND_ICSP)") (class "Default")
      (node (ref "U$1") (pin "GND_ICSP") (pinfunction "GND_ICSP_GND_ICSP") (pintype "bidirectional"))
    )
    (net (code "144") (name "unconnected-(U$1-PadIOREF)") (class "Default")
      (node (ref "U$1") (pin "IOREF") (pinfunction "IOREF_IOREF") (pintype "bidirectional"))
    )
    (net (code "145") (name "unconnected-(U$1-PadNC)") (class "Default")
      (node (ref "U$1") (pin "NC") (pinfunction "NC_NC") (pintype "bidirectional"))
    )
    (net (code "146") (name "unconnected-(U$1-PadRESET)") (class "Default")
      (node (ref "U$1") (pin "RESET") (pinfunction "RESET_RESET") (pintype "bidirectional"))
    )
    (net (code "147") (name "unconnected-(U$1-PadRESET_DEBUG)") (class "Default")
      (node (ref "U$1") (pin "RESET_DEBUG") (pinfunction "RESET_DEBUG_RESET_DEBUG") (pintype "bidirectional"))
    )
    (net (code "148") (name "unconnected-(U$1-PadRESET_ICSP)") (class "Default")
      (node (ref "U$1") (pin "RESET_ICSP") (pinfunction "RESET_ICSP_RESET_ICSP") (pintype "bidirectional"))
    )
    (net (code "149") (name "unconnected-(U$1-PadSCL)") (class "Default")
      (node (ref "U$1") (pin "SCL") (pinfunction "SCL_SCL") (pintype "bidirectional"))
    )
    (net (code "150") (name "unconnected-(U$1-PadSCL1)") (class "Default")
      (node (ref "U$1") (pin "SCL1") (pinfunction "SCL1_SCL1") (pintype "bidirectional"))
    )
    (net (code "151") (name "unconnected-(U$1-PadSDA)") (class "Default")
      (node (ref "U$1") (pin "SDA") (pinfunction "SDA_SDA") (pintype "bidirectional"))
    )
    (net (code "152") (name "unconnected-(U$1-PadSDA1)") (class "Default")
      (node (ref "U$1") (pin "SDA1") (pinfunction "SDA1_SDA1") (pintype "bidirectional"))
    )
    (net (code "153") (name "unconnected-(U$1-PadSWCLK_DEBUG)") (class "Default")
      (node (ref "U$1") (pin "SWCLK_DEBUG") (pinfunction "SWCLK_DEBUG_SWCLK_DEBUG") (pintype "bidirectional"))
    )
    (net (code "154") (name "unconnected-(U$1-PadSWDIO_DEBUG)") (class "Default")
      (node (ref "U$1") (pin "SWDIO_DEBUG") (pinfunction "SWDIO_DEBUG_SWDIO_DEBUG") (pintype "bidirectional"))
    )
    (net (code "155") (name "unconnected-(U2-DAT1-Pad8)") (class "Default")
      (node (ref "U2") (pin "8") (pinfunction "DAT1_8") (pintype "bidirectional"))
    )
    (net (code "156") (name "unconnected-(U2-DAT2-Pad9)") (class "Default")
      (node (ref "U2") (pin "9") (pinfunction "DAT2_9") (pintype "bidirectional"))
    )
    (net (code "157") (name "unconnected-(U2-PadCD)") (class "Default")
      (node (ref "U2") (pin "CD") (pinfunction "CD_CD") (pintype "bidirectional"))
    )
    (net (code "158") (name "unconnected-(U2-PadWP)") (class "Default")
      (node (ref "U2") (pin "WP") (pinfunction "WP_WP") (pintype "bidirectional"))
    )
    (net (code "159") (name "unconnected-(U2-SH-PadSH@1)") (class "Default")
      (node (ref "U2") (pin "SH@1") (pinfunction "SH_SH@1") (pintype "bidirectional"))
    )
    (net (code "160") (name "unconnected-(U2-SH-PadSH@2)") (class "Default")
      (node (ref "U2") (pin "SH@2") (pinfunction "SH_SH@2") (pintype "bidirectional"))
    )
    (net (code "161") (name "unconnected-(U3-CTS-Pad12)") (class "Default")
      (node (ref "U3") (pin "12") (pinfunction "CTS_12") (pintype "output"))
    )
    (net (code "162") (name "unconnected-(U3-DIO0-Pad20)") (class "Default")
      (node (ref "U3") (pin "20") (pinfunction "DIO0_20") (pintype "bidirectional"))
    )
    (net (code "163") (name "unconnected-(U3-DIO1-Pad19)") (class "Default")
      (node (ref "U3") (pin "19") (pinfunction "DIO1_19") (pintype "bidirectional"))
    )
    (net (code "164") (name "unconnected-(U3-DIO2-Pad18)") (class "Default")
      (node (ref "U3") (pin "18") (pinfunction "DIO2_18") (pintype "bidirectional"))
    )
    (net (code "165") (name "unconnected-(U3-DIO3-Pad17)") (class "Default")
      (node (ref "U3") (pin "17") (pinfunction "DIO3_17") (pintype "bidirectional"))
    )
    (net (code "166") (name "unconnected-(U3-DIO4-Pad11)") (class "Default")
      (node (ref "U3") (pin "11") (pinfunction "DIO4_11") (pintype "bidirectional"))
    )
    (net (code "167") (name "unconnected-(U3-DIO5-Pad15)") (class "Default")
      (node (ref "U3") (pin "15") (pinfunction "DIO5_15") (pintype "bidirectional"))
    )
    (net (code "168") (name "unconnected-(U3-DIO9-Pad13)") (class "Default")
      (node (ref "U3") (pin "13") (pinfunction "DIO9_13") (pintype "bidirectional"))
    )
    (net (code "169") (name "unconnected-(U3-DIO11-Pad7)") (class "Default")
      (node (ref "U3") (pin "7") (pinfunction "DIO11_7") (pintype "bidirectional"))
    )
    (net (code "170") (name "unconnected-(U3-DIO12-Pad4)") (class "Default")
      (node (ref "U3") (pin "4") (pinfunction "DIO12_4") (pintype "bidirectional"))
    )
    (net (code "171") (name "unconnected-(U3-DTR-Pad9)") (class "Default")
      (node (ref "U3") (pin "9") (pinfunction "DTR_9") (pintype "bidirectional"))
    )
    (net (code "172") (name "unconnected-(U3-RES-Pad8)") (class "Default")
      (node (ref "U3") (pin "8") (pinfunction "RES_8") (pintype "bidirectional"))
    )
    (net (code "173") (name "unconnected-(U3-RES-Pad14)") (class "Default")
      (node (ref "U3") (pin "14") (pinfunction "RES_14") (pintype "bidirectional"))
    )
    (net (code "174") (name "unconnected-(U3-RESET-Pad5)") (class "Default")
      (node (ref "U3") (pin "5") (pinfunction "RESET_5") (pintype "input"))
    )
    (net (code "175") (name "unconnected-(U3-RSSI-Pad6)") (class "Default")
      (node (ref "U3") (pin "6") (pinfunction "RSSI_6") (pintype "bidirectional"))
    )
    (net (code "176") (name "unconnected-(U3-RTS-Pad16)") (class "Default")
      (node (ref "U3") (pin "16") (pinfunction "RTS_16") (pintype "input"))
    )
  )
)
